# multi_sensor.net
KiCad netlist of a schematic drawn in EAGLE
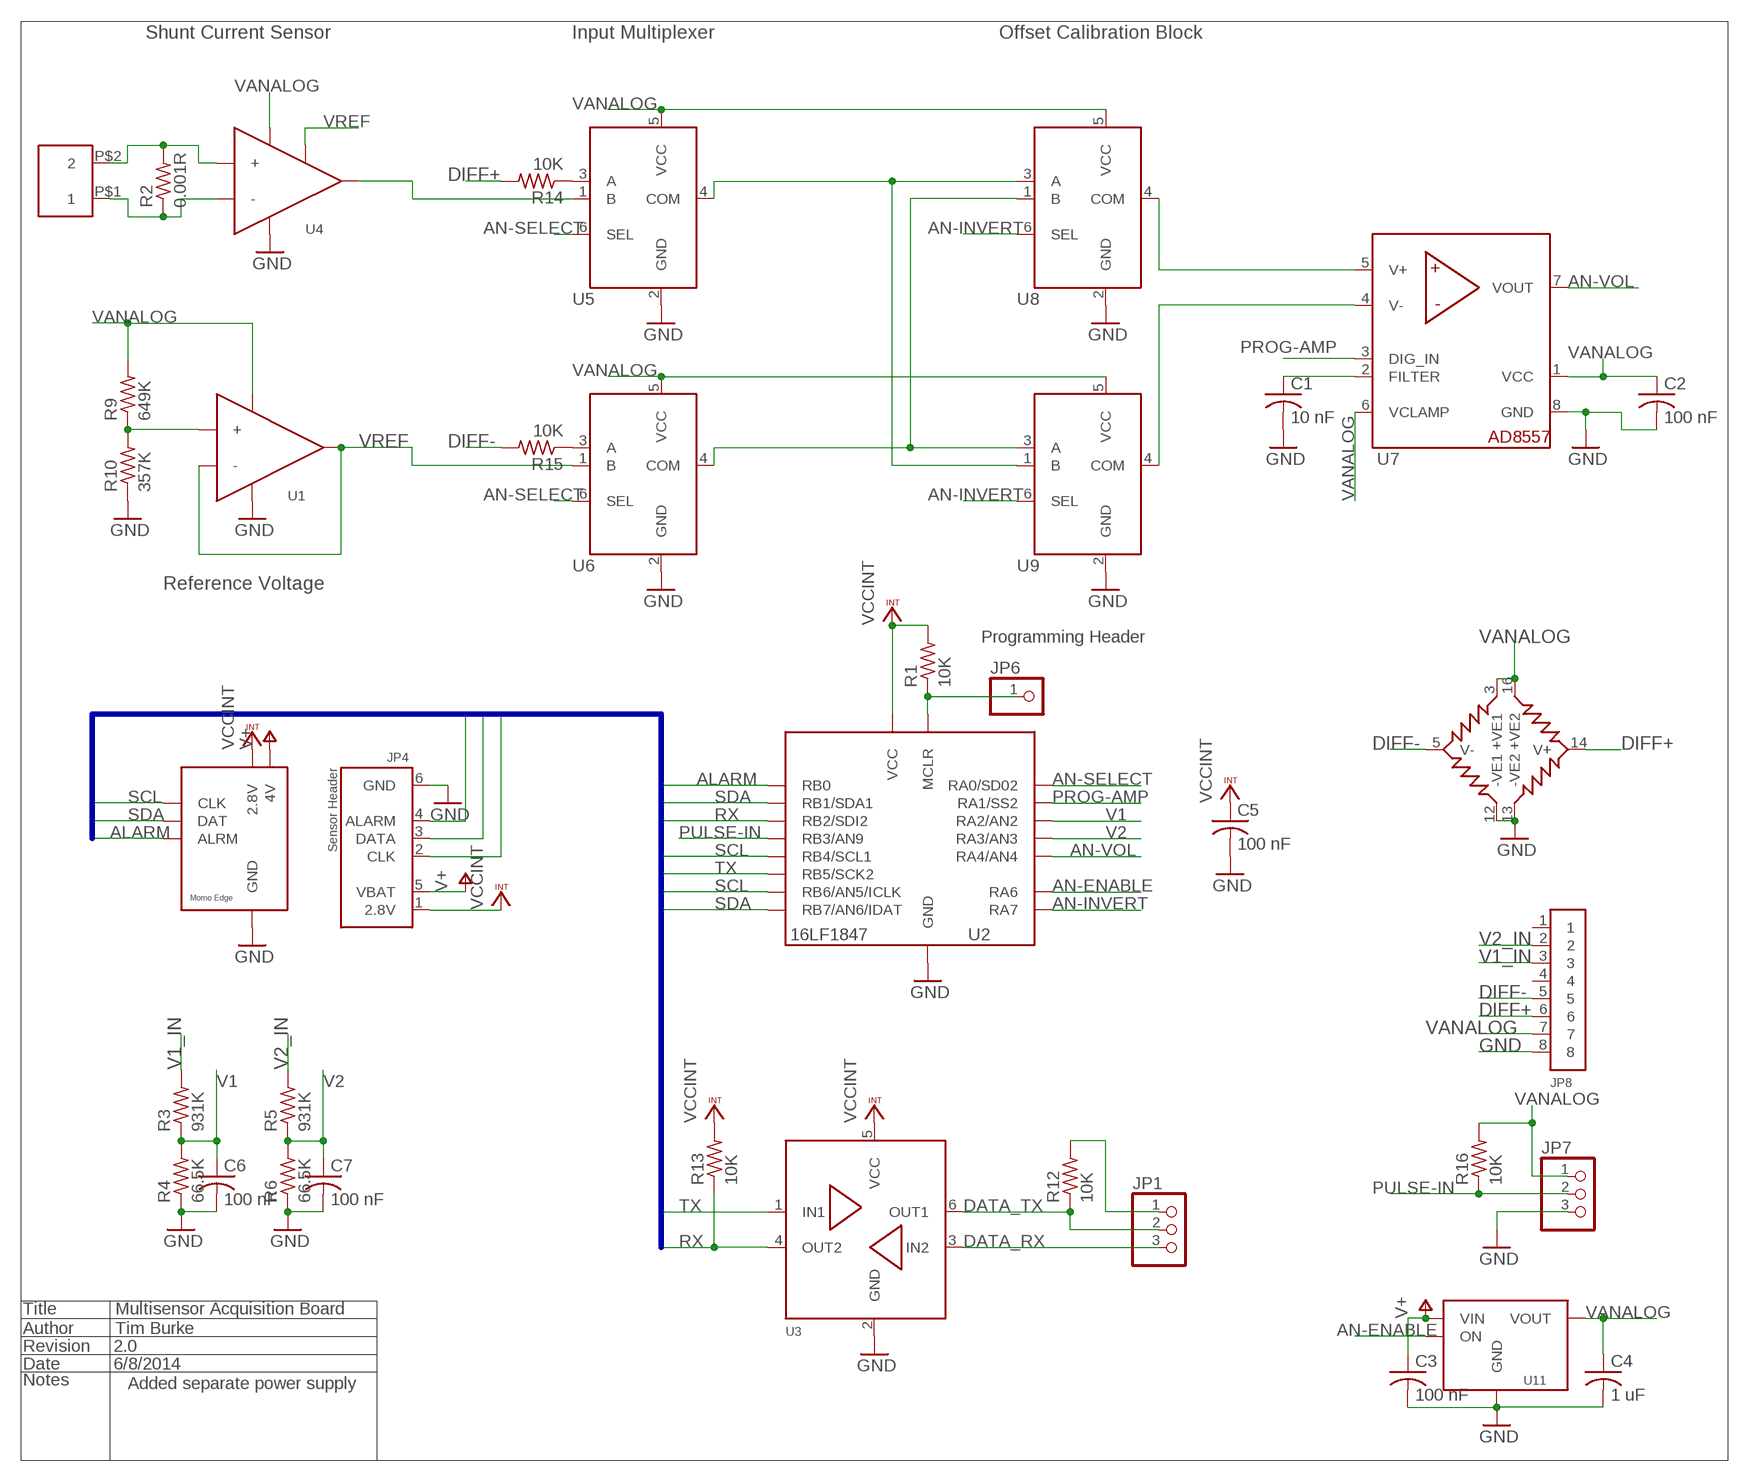
[diagram p0: schematic, sheet 1]

(export (version "E")
  (design (tool "Eeschema 10.0.6"))
  (components
    (comp (ref "C1")
      (value "10 nF")
      (footprint "eagle-import:C0402")
      (libsource (lib "eagle-import") (part "C-USC0402"))
    )
    (comp (ref "C2")
      (value "100 nF")
      (footprint "eagle-import:C0402K")
      (libsource (lib "eagle-import") (part "C-USC0402K"))
    )
    (comp (ref "C3")
      (value "100 nF")
      (footprint "eagle-import:C0402K")
      (libsource (lib "eagle-import") (part "C-USC0402K"))
    )
    (comp (ref "C4")
      (value "1 uF")
      (footprint "eagle-import:C0402K")
      (libsource (lib "eagle-import") (part "C-USC0402K"))
    )
    (comp (ref "C5")
      (value "100 nF")
      (footprint "eagle-import:C0402K")
      (libsource (lib "eagle-import") (part "C-USC0402K"))
    )
    (comp (ref "C6")
      (value "100 nF")
      (footprint "eagle-import:C0402K")
      (libsource (lib "eagle-import") (part "C-USC0402K"))
    )
    (comp (ref "C7")
      (value "100 nF")
      (footprint "eagle-import:C0402K")
      (libsource (lib "eagle-import") (part "C-USC0402K"))
    )
    (comp (ref "JP1")
      (value "PINHD-1X3")
      (footprint "eagle-import:1X03")
      (libsource (lib "eagle-import") (part "PINHD-1X3"))
    )
    (comp (ref "JP2")
      (value "MOMO-VERT-6M")
      (footprint "eagle-import:1X06")
      (libsource (lib "eagle-import") (part "MOMO-VERT-6M"))
    )
    (comp (ref "JP3")
      (value "5MM-SCREWTERM-2POS")
      (footprint "eagle-import:5MM-SCREWTERM")
      (libsource (lib "eagle-import") (part "5MM-SCREWTERM-2POS"))
    )
    (comp (ref "JP4")
      (value "MOMO-SENSOR-RJ11")
      (footprint "eagle-import:RJ-12")
      (fields (field (name "DIGIKEY-PN") "AE10371-ND"))
      (libsource (lib "eagle-import") (part "MOMO-SENSOR-RJ11"))
    )
    (comp (ref "JP6")
      (value "PINHD-1X1")
      (footprint "eagle-import:1X01")
      (libsource (lib "eagle-import") (part "PINHD-1X1"))
    )
    (comp (ref "JP7")
      (value "PINHD-1X3")
      (footprint "eagle-import:1X03")
      (libsource (lib "eagle-import") (part "PINHD-1X3"))
    )
    (comp (ref "JP8")
      (value "8PIN-TERMBLOCK-PUSH")
      (footprint "eagle-import:8-PIN-TERMBLOCK-PUSH")
      (libsource (lib "eagle-import") (part "8PIN-TERMBLOCK-PUSH"))
    )
    (comp (ref "R1")
      (value "10K")
      (footprint "eagle-import:R0603")
      (libsource (lib "eagle-import") (part "R-US_R0603"))
    )
    (comp (ref "R2")
      (value "0.001R")
      (footprint "eagle-import:R2512")
      (libsource (lib "eagle-import") (part "R-US_R2512"))
    )
    (comp (ref "R3")
      (value "931K")
      (footprint "eagle-import:R0603")
      (libsource (lib "eagle-import") (part "R-US_R0603"))
    )
    (comp (ref "R4")
      (value "66.5K")
      (footprint "eagle-import:R0603")
      (libsource (lib "eagle-import") (part "R-US_R0603"))
    )
    (comp (ref "R5")
      (value "931K")
      (footprint "eagle-import:R0603")
      (libsource (lib "eagle-import") (part "R-US_R0603"))
    )
    (comp (ref "R6")
      (value "66.5K")
      (footprint "eagle-import:R0603")
      (libsource (lib "eagle-import") (part "R-US_R0603"))
    )
    (comp (ref "R9")
      (value "649K")
      (footprint "eagle-import:R0603")
      (libsource (lib "eagle-import") (part "R-US_R0603"))
    )
    (comp (ref "R10")
      (value "357K")
      (footprint "eagle-import:R0603")
      (libsource (lib "eagle-import") (part "R-US_R0603"))
    )
    (comp (ref "R12")
      (value "10K")
      (footprint "eagle-import:R0603")
      (libsource (lib "eagle-import") (part "R-US_R0603"))
    )
    (comp (ref "R13")
      (value "10K")
      (footprint "eagle-import:R0603")
      (libsource (lib "eagle-import") (part "R-US_R0603"))
    )
    (comp (ref "R14")
      (value "10K")
      (footprint "eagle-import:R0603")
      (libsource (lib "eagle-import") (part "R-US_R0603"))
    )
    (comp (ref "R15")
      (value "10K")
      (footprint "eagle-import:R0603")
      (libsource (lib "eagle-import") (part "R-US_R0603"))
    )
    (comp (ref "R16")
      (value "10K")
      (footprint "eagle-import:R0603")
      (libsource (lib "eagle-import") (part "R-US_R0603"))
    )
    (comp (ref "U1")
      (value "MCP6001U")
      (footprint "eagle-import:SOT23-5L")
      (libsource (lib "eagle-import") (part "MCP6001U"))
    )
    (comp (ref "U2")
      (value "16LF1847")
      (footprint "eagle-import:SSOP20")
      (libsource (lib "eagle-import") (part "16LF1847"))
    )
    (comp (ref "U3")
      (value "DUAL-BUFFER-OD-NC7WZ07")
      (footprint "eagle-import:SC70-6L")
      (libsource (lib "eagle-import") (part "DUAL-BUFFER-OD-NC7WZ07"))
    )
    (comp (ref "U4")
      (value "LT1990")
      (footprint "eagle-import:SOP08")
      (libsource (lib "eagle-import") (part "LT1990"))
    )
    (comp (ref "U5")
      (value "2:1-MUX")
      (footprint "eagle-import:SOT363_INFINEON")
      (libsource (lib "eagle-import") (part "2{colon}1-MUX"))
    )
    (comp (ref "U6")
      (value "2:1-MUX")
      (footprint "eagle-import:SOT363_INFINEON")
      (libsource (lib "eagle-import") (part "2{colon}1-MUX"))
    )
    (comp (ref "U7")
      (value "AD8557-DIGITRIM-OPAMP")
      (footprint "eagle-import:SOIC8")
      (libsource (lib "eagle-import") (part "AD8557-DIGITRIM-OPAMP"))
    )
    (comp (ref "U8")
      (value "2:1-MUX")
      (footprint "eagle-import:SOT363_INFINEON")
      (libsource (lib "eagle-import") (part "2{colon}1-MUX"))
    )
    (comp (ref "U9")
      (value "2:1-MUX")
      (footprint "eagle-import:SOT363_INFINEON")
      (libsource (lib "eagle-import") (part "2{colon}1-MUX"))
    )
    (comp (ref "U10")
      (value "SM5470-DIFF-PRESS-SENSOR")
      (footprint "eagle-import:SO16W")
      (fields (field (name "MPN") "SM5470"))
      (libsource (lib "eagle-import") (part "SM5470-DIFF-PRESS-SENSOR"))
    )
    (comp (ref "U11")
      (value "TCR2EF28-LINREG")
      (footprint "eagle-import:SC74A-5PIN")
      (libsource (lib "eagle-import") (part "TCR2EF28-LINREG"))
    )
  )
  (nets
    (net (code "1") (name "/ALARM") (class "Default")
      (node (ref "JP2") (pin "5") (pinfunction "ALRM_5") (pintype "bidirectional"))
      (node (ref "JP4") (pin "4") (pinfunction "ALARM_4") (pintype "bidirectional"))
      (node (ref "U2") (pin "7") (pinfunction "RB0_7") (pintype "bidirectional"))
    )
    (net (code "2") (name "/AN-ENABLE") (class "Default")
      (node (ref "U11") (pin "3") (pinfunction "ON_3") (pintype "bidirectional"))
      (node (ref "U2") (pin "17") (pinfunction "RA6_17") (pintype "bidirectional"))
    )
    (net (code "3") (name "/AN-INVERT") (class "Default")
      (node (ref "U2") (pin "18") (pinfunction "RA7_18") (pintype "bidirectional"))
      (node (ref "U8") (pin "6") (pinfunction "SEL_6") (pintype "bidirectional"))
      (node (ref "U9") (pin "6") (pinfunction "SEL_6") (pintype "bidirectional"))
    )
    (net (code "4") (name "/AN-SELECT") (class "Default")
      (node (ref "U2") (pin "19") (pinfunction "RA0/SD02_19") (pintype "bidirectional"))
      (node (ref "U5") (pin "6") (pinfunction "SEL_6") (pintype "bidirectional"))
      (node (ref "U6") (pin "6") (pinfunction "SEL_6") (pintype "bidirectional"))
    )
    (net (code "5") (name "/AN-VOL") (class "Default")
      (node (ref "U2") (pin "3") (pinfunction "RA4/AN4_3") (pintype "bidirectional"))
      (node (ref "U7") (pin "7") (pinfunction "VOUT_7") (pintype "bidirectional"))
    )
    (net (code "6") (name "/DATA_RX") (class "Default")
      (node (ref "JP1") (pin "3") (pinfunction "3_3") (pintype "passive"))
      (node (ref "U3") (pin "3") (pinfunction "IN2_3") (pintype "bidirectional"))
    )
    (net (code "7") (name "/DATA_TX") (class "Default")
      (node (ref "JP1") (pin "2") (pinfunction "2_2") (pintype "passive"))
      (node (ref "R12") (pin "1") (pinfunction "1_1") (pintype "passive"))
      (node (ref "U3") (pin "6") (pinfunction "OUT1_6") (pintype "bidirectional"))
    )
    (net (code "8") (name "/DIFF+") (class "Default")
      (node (ref "JP8") (pin "6") (pinfunction "6_6") (pintype "passive"))
      (node (ref "R14") (pin "2") (pinfunction "2_2") (pintype "passive"))
      (node (ref "U10") (pin "14") (pinfunction "V+_14") (pintype "passive"))
    )
    (net (code "9") (name "/DIFF-") (class "Default")
      (node (ref "JP8") (pin "5") (pinfunction "5_5") (pintype "passive"))
      (node (ref "R15") (pin "2") (pinfunction "2_2") (pintype "passive"))
      (node (ref "U10") (pin "5") (pinfunction "V-_5") (pintype "passive"))
    )
    (net (code "10") (name "/PROG-AMP") (class "Default")
      (node (ref "U2") (pin "20") (pinfunction "RA1/SS2_20") (pintype "bidirectional"))
      (node (ref "U7") (pin "3") (pinfunction "DIG_IN_3") (pintype "bidirectional"))
    )
    (net (code "11") (name "/PULSE-IN") (class "Default")
      (node (ref "JP7") (pin "2") (pinfunction "2_2") (pintype "passive"))
      (node (ref "R16") (pin "1") (pinfunction "1_1") (pintype "passive"))
      (node (ref "U2") (pin "10") (pinfunction "RB3/AN9_10") (pintype "bidirectional"))
    )
    (net (code "12") (name "/RX") (class "Default")
      (node (ref "R13") (pin "1") (pinfunction "1_1") (pintype "passive"))
      (node (ref "U2") (pin "9") (pinfunction "RB2/SDI2_9") (pintype "bidirectional"))
      (node (ref "U3") (pin "4") (pinfunction "OUT2_4") (pintype "bidirectional"))
    )
    (net (code "13") (name "/SCL") (class "Default")
      (node (ref "JP2") (pin "3") (pinfunction "CLK_3") (pintype "bidirectional"))
      (node (ref "JP4") (pin "2") (pinfunction "CLK_2") (pintype "bidirectional"))
      (node (ref "U2") (pin "11") (pinfunction "RB4/SCL1_11") (pintype "bidirectional"))
      (node (ref "U2") (pin "13") (pinfunction "RB6/AN5/ICLK_13") (pintype "bidirectional"))
    )
    (net (code "14") (name "/SDA") (class "Default")
      (node (ref "JP2") (pin "4") (pinfunction "DAT_4") (pintype "bidirectional"))
      (node (ref "JP4") (pin "3") (pinfunction "DATA_3") (pintype "bidirectional"))
      (node (ref "U2") (pin "14") (pinfunction "RB7/AN6/IDAT_14") (pintype "bidirectional"))
      (node (ref "U2") (pin "8") (pinfunction "RB1/SDA1_8") (pintype "bidirectional"))
    )
    (net (code "15") (name "/TX") (class "Default")
      (node (ref "U2") (pin "12") (pinfunction "RB5/SCK2_12") (pintype "bidirectional"))
      (node (ref "U3") (pin "1") (pinfunction "IN1_1") (pintype "bidirectional"))
    )
    (net (code "16") (name "/V1") (class "Default")
      (node (ref "C6") (pin "1") (pinfunction "1_1") (pintype "passive"))
      (node (ref "R3") (pin "1") (pinfunction "1_1") (pintype "passive"))
      (node (ref "R4") (pin "2") (pinfunction "2_2") (pintype "passive"))
      (node (ref "U2") (pin "1") (pinfunction "RA2/AN2_1") (pintype "bidirectional"))
    )
    (net (code "17") (name "/V1_IN") (class "Default")
      (node (ref "JP8") (pin "3") (pinfunction "3_3") (pintype "passive"))
      (node (ref "R3") (pin "2") (pinfunction "2_2") (pintype "passive"))
    )
    (net (code "18") (name "/V2") (class "Default")
      (node (ref "C7") (pin "1") (pinfunction "1_1") (pintype "passive"))
      (node (ref "R5") (pin "1") (pinfunction "1_1") (pintype "passive"))
      (node (ref "R6") (pin "2") (pinfunction "2_2") (pintype "passive"))
      (node (ref "U2") (pin "2") (pinfunction "RA3/AN3_2") (pintype "bidirectional"))
    )
    (net (code "19") (name "/V2_IN") (class "Default")
      (node (ref "JP8") (pin "2") (pinfunction "2_2") (pintype "passive"))
      (node (ref "R5") (pin "2") (pinfunction "2_2") (pintype "passive"))
    )
    (net (code "20") (name "/VANALOG") (class "Default")
      (node (ref "C2") (pin "1") (pinfunction "1_1") (pintype "passive"))
      (node (ref "C4") (pin "1") (pinfunction "1_1") (pintype "passive"))
      (node (ref "JP7") (pin "1") (pinfunction "1_1") (pintype "passive"))
      (node (ref "JP8") (pin "7") (pinfunction "7_7") (pintype "passive"))
      (node (ref "R16") (pin "2") (pinfunction "2_2") (pintype "passive"))
      (node (ref "R9") (pin "2") (pinfunction "2_2") (pintype "passive"))
      (node (ref "U1") (pin "5") (pinfunction "VCC_5") (pintype "power_in"))
      (node (ref "U10") (pin "16") (pinfunction "+VE2_16") (pintype "passive"))
      (node (ref "U10") (pin "3") (pinfunction "+VE1_3") (pintype "passive"))
      (node (ref "U11") (pin "5") (pinfunction "VOUT_5") (pintype "power_in"))
      (node (ref "U4") (pin "7") (pinfunction "VCC_7") (pintype "power_in"))
      (node (ref "U5") (pin "5") (pinfunction "VCC_5") (pintype "bidirectional"))
      (node (ref "U6") (pin "5") (pinfunction "VCC_5") (pintype "bidirectional"))
      (node (ref "U7") (pin "1") (pinfunction "VCC_1") (pintype "bidirectional"))
      (node (ref "U7") (pin "6") (pinfunction "VCLAMP_6") (pintype "bidirectional"))
      (node (ref "U8") (pin "5") (pinfunction "VCC_5") (pintype "bidirectional"))
      (node (ref "U9") (pin "5") (pinfunction "VCC_5") (pintype "bidirectional"))
    )
    (net (code "21") (name "/VREF") (class "Default")
      (node (ref "U1") (pin "3") (pinfunction "-_3") (pintype "input"))
      (node (ref "U1") (pin "4") (pinfunction "OUT_4") (pintype "output"))
      (node (ref "U4") (pin "1") (pinfunction "SHUT_1") (pintype "input"))
      (node (ref "U6") (pin "1") (pinfunction "B_1") (pintype "bidirectional"))
    )
    (net (code "22") (name "GND") (class "Default")
      (node (ref "C1") (pin "2") (pinfunction "2_2") (pintype "passive"))
      (node (ref "C2") (pin "2") (pinfunction "2_2") (pintype "passive"))
      (node (ref "C3") (pin "2") (pinfunction "2_2") (pintype "passive"))
      (node (ref "C4") (pin "2") (pinfunction "2_2") (pintype "passive"))
      (node (ref "C5") (pin "2") (pinfunction "2_2") (pintype "passive"))
      (node (ref "C6") (pin "2") (pinfunction "2_2") (pintype "passive"))
      (node (ref "C7") (pin "2") (pinfunction "2_2") (pintype "passive"))
      (node (ref "JP2") (pin "7") (pinfunction "GND_7") (pintype "power_in"))
      (node (ref "JP4") (pin "6") (pinfunction "GND_6") (pintype "bidirectional"))
      (node (ref "JP7") (pin "3") (pinfunction "3_3") (pintype "passive"))
      (node (ref "JP8") (pin "8") (pinfunction "8_8") (pintype "passive"))
      (node (ref "R10") (pin "1") (pinfunction "1_1") (pintype "passive"))
      (node (ref "R4") (pin "1") (pinfunction "1_1") (pintype "passive"))
      (node (ref "R6") (pin "1") (pinfunction "1_1") (pintype "passive"))
      (node (ref "U1") (pin "2") (pinfunction "GND_2") (pintype "power_in"))
      (node (ref "U10") (pin "12") (pinfunction "-VE1_12") (pintype "passive"))
      (node (ref "U10") (pin "13") (pinfunction "-VE2_13") (pintype "passive"))
      (node (ref "U11") (pin "2") (pinfunction "GND_2") (pintype "power_in"))
      (node (ref "U2") (pin "5") (pinfunction "GND_5") (pintype "power_in"))
      (node (ref "U2") (pin "6") (pinfunction "GND_6") (pintype "power_in"))
      (node (ref "U3") (pin "2") (pinfunction "GND_2") (pintype "bidirectional"))
      (node (ref "U4") (pin "4") (pinfunction "GND_4") (pintype "power_in"))
      (node (ref "U5") (pin "2") (pinfunction "GND_2") (pintype "bidirectional"))
      (node (ref "U6") (pin "2") (pinfunction "GND_2") (pintype "bidirectional"))
      (node (ref "U7") (pin "8") (pinfunction "GND_8") (pintype "bidirectional"))
      (node (ref "U8") (pin "2") (pinfunction "GND_2") (pintype "bidirectional"))
      (node (ref "U9") (pin "2") (pinfunction "GND_2") (pintype "bidirectional"))
    )
    (net (code "23") (name "Net-(JP1-Pad1)") (class "Default")
      (node (ref "JP1") (pin "1") (pinfunction "1_1") (pintype "passive"))
      (node (ref "R12") (pin "2") (pinfunction "2_2") (pintype "passive"))
    )
    (net (code "24") (name "Net-(JP3-1)") (class "Default")
      (node (ref "JP3") (pin "P$1") (pinfunction "1_P$1") (pintype "passive"))
      (node (ref "R2") (pin "1") (pinfunction "1_1") (pintype "passive"))
      (node (ref "U4") (pin "2") (pinfunction "-_2") (pintype "input"))
    )
    (net (code "25") (name "Net-(JP3-2)") (class "Default")
      (node (ref "JP3") (pin "P$2") (pinfunction "2_P$2") (pintype "passive"))
      (node (ref "R2") (pin "2") (pinfunction "2_2") (pintype "passive"))
      (node (ref "U4") (pin "3") (pinfunction "+_3") (pintype "input"))
    )
    (net (code "26") (name "Net-(U1-+)") (class "Default")
      (node (ref "R10") (pin "2") (pinfunction "2_2") (pintype "passive"))
      (node (ref "R9") (pin "1") (pinfunction "1_1") (pintype "passive"))
      (node (ref "U1") (pin "1") (pinfunction "+_1") (pintype "input"))
    )
    (net (code "27") (name "Net-(U2-MCLR)") (class "Default")
      (node (ref "JP6") (pin "1") (pinfunction "1_1") (pintype "passive"))
      (node (ref "R1") (pin "1") (pinfunction "1_1") (pintype "passive"))
      (node (ref "U2") (pin "4") (pinfunction "MCLR_4") (pintype "bidirectional"))
    )
    (net (code "28") (name "Net-(U4-OUT)") (class "Default")
      (node (ref "U4") (pin "6") (pinfunction "OUT_6") (pintype "output"))
      (node (ref "U5") (pin "1") (pinfunction "B_1") (pintype "bidirectional"))
    )
    (net (code "29") (name "Net-(U5-A)") (class "Default")
      (node (ref "R14") (pin "1") (pinfunction "1_1") (pintype "passive"))
      (node (ref "U5") (pin "3") (pinfunction "A_3") (pintype "bidirectional"))
    )
    (net (code "30") (name "Net-(U5-COM)") (class "Default")
      (node (ref "U5") (pin "4") (pinfunction "COM_4") (pintype "bidirectional"))
      (node (ref "U8") (pin "3") (pinfunction "A_3") (pintype "bidirectional"))
      (node (ref "U9") (pin "1") (pinfunction "B_1") (pintype "bidirectional"))
    )
    (net (code "31") (name "Net-(U6-A)") (class "Default")
      (node (ref "R15") (pin "1") (pinfunction "1_1") (pintype "passive"))
      (node (ref "U6") (pin "3") (pinfunction "A_3") (pintype "bidirectional"))
    )
    (net (code "32") (name "Net-(U6-COM)") (class "Default")
      (node (ref "U6") (pin "4") (pinfunction "COM_4") (pintype "bidirectional"))
      (node (ref "U8") (pin "1") (pinfunction "B_1") (pintype "bidirectional"))
      (node (ref "U9") (pin "3") (pinfunction "A_3") (pintype "bidirectional"))
    )
    (net (code "33") (name "Net-(U7-FILTER)") (class "Default")
      (node (ref "C1") (pin "1") (pinfunction "1_1") (pintype "passive"))
      (node (ref "U7") (pin "2") (pinfunction "FILTER_2") (pintype "bidirectional"))
    )
    (net (code "34") (name "Net-(U7-V+)") (class "Default")
      (node (ref "U7") (pin "5") (pinfunction "V+_5") (pintype "bidirectional"))
      (node (ref "U8") (pin "4") (pinfunction "COM_4") (pintype "bidirectional"))
    )
    (net (code "35") (name "Net-(U7-V-)") (class "Default")
      (node (ref "U7") (pin "4") (pinfunction "V-_4") (pintype "bidirectional"))
      (node (ref "U9") (pin "4") (pinfunction "COM_4") (pintype "bidirectional"))
    )
    (net (code "36") (name "V+") (class "Default")
      (node (ref "C3") (pin "1") (pinfunction "1_1") (pintype "passive"))
      (node (ref "JP2") (pin "6") (pinfunction "4V_6") (pintype "power_in"))
      (node (ref "JP4") (pin "5") (pinfunction "VBAT_5") (pintype "bidirectional"))
      (node (ref "U11") (pin "1") (pinfunction "VIN_1") (pintype "power_in"))
    )
    (net (code "37") (name "VCCINT") (class "Default")
      (node (ref "C5") (pin "1") (pinfunction "1_1") (pintype "passive"))
      (node (ref "JP2") (pin "1") (pinfunction "2.8V_1") (pintype "power_in"))
      (node (ref "JP4") (pin "1") (pinfunction "2.8V_1") (pintype "bidirectional"))
      (node (ref "R1") (pin "2") (pinfunction "2_2") (pintype "passive"))
      (node (ref "R13") (pin "2") (pinfunction "2_2") (pintype "passive"))
      (node (ref "U2") (pin "15") (pinfunction "VCC_15") (pintype "power_in"))
      (node (ref "U2") (pin "16") (pinfunction "VCC_16") (pintype "power_in"))
      (node (ref "U3") (pin "5") (pinfunction "VCC_5") (pintype "bidirectional"))
    )
    (net (code "38") (name "unconnected-(JP8-Pad1)") (class "Default")
      (node (ref "JP8") (pin "1") (pinfunction "1_1") (pintype "passive"))
    )
    (net (code "39") (name "unconnected-(JP8-Pad4)") (class "Default")
      (node (ref "JP8") (pin "4") (pinfunction "4_4") (pintype "passive"))
    )
  )
)
